# FC_Conn.net
KiCad netlist of a schematic drawn in Altium Designer
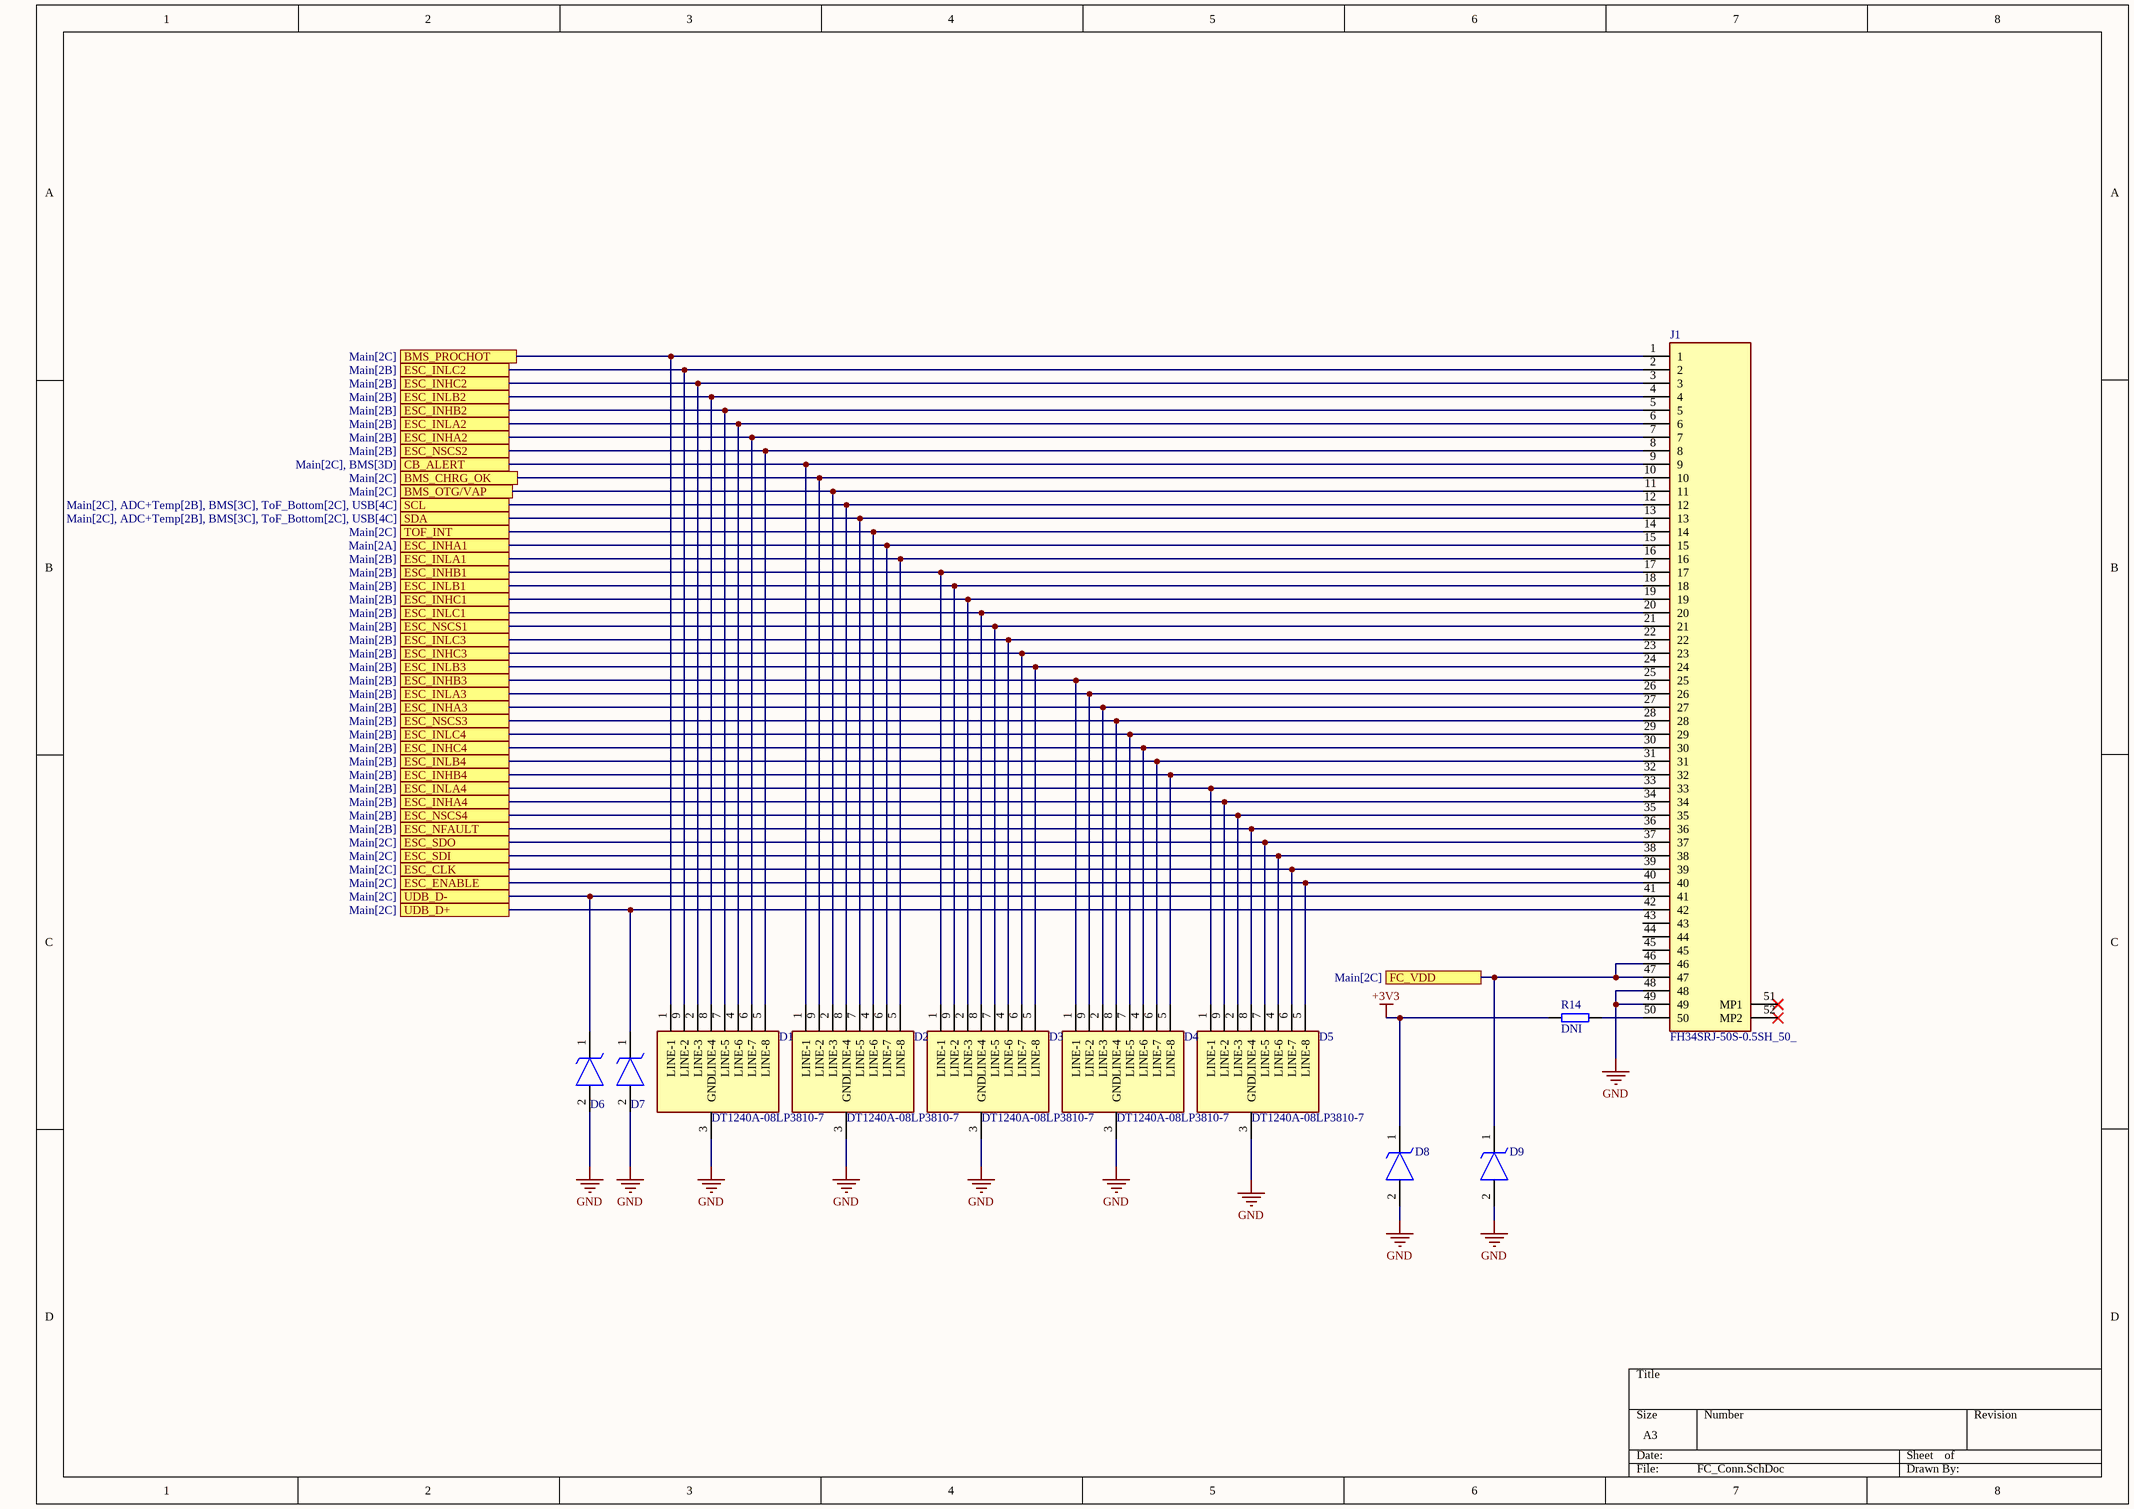
[diagram p0: FC_Conn.SchDoc]

(export (version "E")
  (design (tool "Eeschema 10.0.6"))
  (components
    (comp (ref "D1")
      (value "DT1240A-08LP3810-7")
      (footprint "SamacSys:DT1240A08LP38107")
      (description "TVS Diode (Uni-directional)")
      (fields (field (name "MOUSER PART NUMBER") "621-DT1240A08LP38107"))
      (libsource (lib "SamacSys") (part "DT1240A-08LP3810-7"))
    )
    (comp (ref "D2")
      (value "DT1240A-08LP3810-7")
      (footprint "SamacSys:DT1240A08LP38107")
      (description "TVS Diode (Uni-directional)")
      (fields (field (name "MOUSER PART NUMBER") "621-DT1240A08LP38107"))
      (libsource (lib "SamacSys") (part "DT1240A-08LP3810-7"))
    )
    (comp (ref "D3")
      (value "DT1240A-08LP3810-7")
      (footprint "SamacSys:DT1240A08LP38107")
      (description "TVS Diode (Uni-directional)")
      (fields (field (name "MOUSER PART NUMBER") "621-DT1240A08LP38107"))
      (libsource (lib "SamacSys") (part "DT1240A-08LP3810-7"))
    )
    (comp (ref "D4")
      (value "DT1240A-08LP3810-7")
      (footprint "SamacSys:DT1240A08LP38107")
      (description "TVS Diode (Uni-directional)")
      (fields (field (name "MOUSER PART NUMBER") "621-DT1240A08LP38107"))
      (libsource (lib "SamacSys") (part "DT1240A-08LP3810-7"))
    )
    (comp (ref "D5")
      (value "DT1240A-08LP3810-7")
      (footprint "SamacSys:DT1240A08LP38107")
      (description "TVS Diode (Uni-directional)")
      (fields (field (name "MOUSER PART NUMBER") "621-DT1240A08LP38107"))
      (libsource (lib "SamacSys") (part "DT1240A-08LP3810-7"))
    )
    (comp (ref "D6")
      (value "D1213A-01LP4-7B")
      (footprint "SamacSys:D1213A01LP47B")
      (description "TVS Diode (Uni-directional)")
      (fields (field (name "MOUSER PART NUMBER") "621-D1213A-01LP4-7B"))
      (libsource (lib "*") (part "D1213A-01LP4-7B"))
    )
    (comp (ref "D7")
      (value "D1213A-01LP4-7B")
      (footprint "SamacSys:D1213A01LP47B")
      (description "TVS Diode (Uni-directional)")
      (fields (field (name "MOUSER PART NUMBER") "621-D1213A-01LP4-7B"))
      (libsource (lib "*") (part "D1213A-01LP4-7B"))
    )
    (comp (ref "D8")
      (value "DF2S24FS,L3M")
      (footprint "SamacSys:SODFL1006X45N")
      (description "TVS Diode (Uni-directional)")
      (fields (field (name "MOUSER PART NUMBER") "757-DF2S24FSL3M"))
      (libsource (lib "*") (part "DF2S24FS,L3M"))
    )
    (comp (ref "D9")
      (value "DF2S24FS,L3M")
      (footprint "SamacSys:SODFL1006X45N")
      (description "TVS Diode (Uni-directional)")
      (fields (field (name "MOUSER PART NUMBER") "757-DF2S24FSL3M"))
      (libsource (lib "*") (part "DF2S24FS,L3M"))
    )
    (comp (ref "J1")
      (value "FH34SRJ-50S-0.5SH_50_")
      (footprint "SamacSys:FH34SRJ50S05SH50")
      (description "Connector")
      (fields
        (field (name "MANUFACTURER_PART_NUMBER") "FH34SRJ-50S-0.5SH(50)")
        (field (name "MOUSER PART NUMBER") "798-FH34SRJ50S05SH50")
      )
      (libsource (lib "*") (part "FH34SRJ-50S-0.5SH_50_"))
    )
    (comp (ref "R14")
      (value "DNI")
      (footprint "RES0402")
      (fields (field (name "Comment") "Res0402"))
      (libsource (lib "resistorSMD") (part "Res0402"))
    )
  )
  (nets
    (net (code "1") (name "+3V3") (class "Default")
      (node (ref "D8") (pin "1") (pinfunction "K_1") (pintype "passive"))
      (node (ref "R14") (pin "2") (pinfunction "2_2") (pintype "passive"))
    )
    (net (code "2") (name "/BMS_CHRG_OK") (class "Default")
      (node (ref "D2") (pin "9") (pinfunction "LINE-2_9") (pintype "passive"))
      (node (ref "J1") (pin "10") (pinfunction "10_10") (pintype "passive"))
    )
    (net (code "3") (name "/BMS_OTG{slash}VAP") (class "Default")
      (node (ref "D2") (pin "2") (pinfunction "LINE-3_2") (pintype "passive"))
      (node (ref "J1") (pin "11") (pinfunction "11_11") (pintype "passive"))
    )
    (net (code "4") (name "/BMS_PROCHOT") (class "Default")
      (node (ref "D1") (pin "1") (pinfunction "LINE-1_1") (pintype "passive"))
      (node (ref "J1") (pin "1") (pinfunction "1_1") (pintype "passive"))
    )
    (net (code "5") (name "/CB_ALERT") (class "Default")
      (node (ref "D2") (pin "1") (pinfunction "LINE-1_1") (pintype "passive"))
      (node (ref "J1") (pin "9") (pinfunction "9_9") (pintype "passive"))
    )
    (net (code "6") (name "/ESC_CLK") (class "Default")
      (node (ref "D5") (pin "6") (pinfunction "LINE-7_6") (pintype "passive"))
      (node (ref "J1") (pin "39") (pinfunction "39_39") (pintype "passive"))
    )
    (net (code "7") (name "/ESC_ENABLE") (class "Default")
      (node (ref "D5") (pin "5") (pinfunction "LINE-8_5") (pintype "passive"))
      (node (ref "J1") (pin "40") (pinfunction "40_40") (pintype "passive"))
    )
    (net (code "8") (name "/ESC_INHA1") (class "Default")
      (node (ref "D2") (pin "6") (pinfunction "LINE-7_6") (pintype "passive"))
      (node (ref "J1") (pin "15") (pinfunction "15_15") (pintype "passive"))
    )
    (net (code "9") (name "/ESC_INHA2") (class "Default")
      (node (ref "D1") (pin "6") (pinfunction "LINE-7_6") (pintype "passive"))
      (node (ref "J1") (pin "7") (pinfunction "7_7") (pintype "passive"))
    )
    (net (code "10") (name "/ESC_INHA3") (class "Default")
      (node (ref "D4") (pin "2") (pinfunction "LINE-3_2") (pintype "passive"))
      (node (ref "J1") (pin "27") (pinfunction "27_27") (pintype "passive"))
    )
    (net (code "11") (name "/ESC_INHA4") (class "Default")
      (node (ref "D5") (pin "9") (pinfunction "LINE-2_9") (pintype "passive"))
      (node (ref "J1") (pin "34") (pinfunction "34_34") (pintype "passive"))
    )
    (net (code "12") (name "/ESC_INHB1") (class "Default")
      (node (ref "D3") (pin "1") (pinfunction "LINE-1_1") (pintype "passive"))
      (node (ref "J1") (pin "17") (pinfunction "17_17") (pintype "passive"))
    )
    (net (code "13") (name "/ESC_INHB2") (class "Default")
      (node (ref "D1") (pin "7") (pinfunction "LINE-5_7") (pintype "passive"))
      (node (ref "J1") (pin "5") (pinfunction "5_5") (pintype "passive"))
    )
    (net (code "14") (name "/ESC_INHB3") (class "Default")
      (node (ref "D4") (pin "1") (pinfunction "LINE-1_1") (pintype "passive"))
      (node (ref "J1") (pin "25") (pinfunction "25_25") (pintype "passive"))
    )
    (net (code "15") (name "/ESC_INHB4") (class "Default")
      (node (ref "D4") (pin "5") (pinfunction "LINE-8_5") (pintype "passive"))
      (node (ref "J1") (pin "32") (pinfunction "32_32") (pintype "passive"))
    )
    (net (code "16") (name "/ESC_INHC1") (class "Default")
      (node (ref "D3") (pin "2") (pinfunction "LINE-3_2") (pintype "passive"))
      (node (ref "J1") (pin "19") (pinfunction "19_19") (pintype "passive"))
    )
    (net (code "17") (name "/ESC_INHC2") (class "Default")
      (node (ref "D1") (pin "2") (pinfunction "LINE-3_2") (pintype "passive"))
      (node (ref "J1") (pin "3") (pinfunction "3_3") (pintype "passive"))
    )
    (net (code "18") (name "/ESC_INHC3") (class "Default")
      (node (ref "D3") (pin "6") (pinfunction "LINE-7_6") (pintype "passive"))
      (node (ref "J1") (pin "23") (pinfunction "23_23") (pintype "passive"))
    )
    (net (code "19") (name "/ESC_INHC4") (class "Default")
      (node (ref "D4") (pin "4") (pinfunction "LINE-6_4") (pintype "passive"))
      (node (ref "J1") (pin "30") (pinfunction "30_30") (pintype "passive"))
    )
    (net (code "20") (name "/ESC_INLA1") (class "Default")
      (node (ref "D2") (pin "5") (pinfunction "LINE-8_5") (pintype "passive"))
      (node (ref "J1") (pin "16") (pinfunction "16_16") (pintype "passive"))
    )
    (net (code "21") (name "/ESC_INLA2") (class "Default")
      (node (ref "D1") (pin "4") (pinfunction "LINE-6_4") (pintype "passive"))
      (node (ref "J1") (pin "6") (pinfunction "6_6") (pintype "passive"))
    )
    (net (code "22") (name "/ESC_INLA3") (class "Default")
      (node (ref "D4") (pin "9") (pinfunction "LINE-2_9") (pintype "passive"))
      (node (ref "J1") (pin "26") (pinfunction "26_26") (pintype "passive"))
    )
    (net (code "23") (name "/ESC_INLA4") (class "Default")
      (node (ref "D5") (pin "1") (pinfunction "LINE-1_1") (pintype "passive"))
      (node (ref "J1") (pin "33") (pinfunction "33_33") (pintype "passive"))
    )
    (net (code "24") (name "/ESC_INLB1") (class "Default")
      (node (ref "D3") (pin "9") (pinfunction "LINE-2_9") (pintype "passive"))
      (node (ref "J1") (pin "18") (pinfunction "18_18") (pintype "passive"))
    )
    (net (code "25") (name "/ESC_INLB2") (class "Default")
      (node (ref "D1") (pin "8") (pinfunction "LINE-4_8") (pintype "passive"))
      (node (ref "J1") (pin "4") (pinfunction "4_4") (pintype "passive"))
    )
    (net (code "26") (name "/ESC_INLB3") (class "Default")
      (node (ref "D3") (pin "5") (pinfunction "LINE-8_5") (pintype "passive"))
      (node (ref "J1") (pin "24") (pinfunction "24_24") (pintype "passive"))
    )
    (net (code "27") (name "/ESC_INLB4") (class "Default")
      (node (ref "D4") (pin "6") (pinfunction "LINE-7_6") (pintype "passive"))
      (node (ref "J1") (pin "31") (pinfunction "31_31") (pintype "passive"))
    )
    (net (code "28") (name "/ESC_INLC1") (class "Default")
      (node (ref "D3") (pin "8") (pinfunction "LINE-4_8") (pintype "passive"))
      (node (ref "J1") (pin "20") (pinfunction "20_20") (pintype "passive"))
    )
    (net (code "29") (name "/ESC_INLC2") (class "Default")
      (node (ref "D1") (pin "9") (pinfunction "LINE-2_9") (pintype "passive"))
      (node (ref "J1") (pin "2") (pinfunction "2_2") (pintype "passive"))
    )
    (net (code "30") (name "/ESC_INLC3") (class "Default")
      (node (ref "D3") (pin "4") (pinfunction "LINE-6_4") (pintype "passive"))
      (node (ref "J1") (pin "22") (pinfunction "22_22") (pintype "passive"))
    )
    (net (code "31") (name "/ESC_INLC4") (class "Default")
      (node (ref "D4") (pin "7") (pinfunction "LINE-5_7") (pintype "passive"))
      (node (ref "J1") (pin "29") (pinfunction "29_29") (pintype "passive"))
    )
    (net (code "32") (name "/ESC_NFAULT") (class "Default")
      (node (ref "D5") (pin "8") (pinfunction "LINE-4_8") (pintype "passive"))
      (node (ref "J1") (pin "36") (pinfunction "36_36") (pintype "passive"))
    )
    (net (code "33") (name "/ESC_NSCS1") (class "Default")
      (node (ref "D3") (pin "7") (pinfunction "LINE-5_7") (pintype "passive"))
      (node (ref "J1") (pin "21") (pinfunction "21_21") (pintype "passive"))
    )
    (net (code "34") (name "/ESC_NSCS2") (class "Default")
      (node (ref "D1") (pin "5") (pinfunction "LINE-8_5") (pintype "passive"))
      (node (ref "J1") (pin "8") (pinfunction "8_8") (pintype "passive"))
    )
    (net (code "35") (name "/ESC_NSCS3") (class "Default")
      (node (ref "D4") (pin "8") (pinfunction "LINE-4_8") (pintype "passive"))
      (node (ref "J1") (pin "28") (pinfunction "28_28") (pintype "passive"))
    )
    (net (code "36") (name "/ESC_NSCS4") (class "Default")
      (node (ref "D5") (pin "2") (pinfunction "LINE-3_2") (pintype "passive"))
      (node (ref "J1") (pin "35") (pinfunction "35_35") (pintype "passive"))
    )
    (net (code "37") (name "/ESC_SDI") (class "Default")
      (node (ref "D5") (pin "4") (pinfunction "LINE-6_4") (pintype "passive"))
      (node (ref "J1") (pin "38") (pinfunction "38_38") (pintype "passive"))
    )
    (net (code "38") (name "/ESC_SDO") (class "Default")
      (node (ref "D5") (pin "7") (pinfunction "LINE-5_7") (pintype "passive"))
      (node (ref "J1") (pin "37") (pinfunction "37_37") (pintype "passive"))
    )
    (net (code "39") (name "/FC_VDD") (class "Default")
      (node (ref "D9") (pin "1") (pinfunction "K_1") (pintype "passive"))
      (node (ref "J1") (pin "46") (pinfunction "46_46") (pintype "passive"))
      (node (ref "J1") (pin "47") (pinfunction "47_47") (pintype "passive"))
    )
    (net (code "40") (name "/SCL") (class "Default")
      (node (ref "D2") (pin "8") (pinfunction "LINE-4_8") (pintype "passive"))
      (node (ref "J1") (pin "12") (pinfunction "12_12") (pintype "passive"))
    )
    (net (code "41") (name "/SDA") (class "Default")
      (node (ref "D2") (pin "7") (pinfunction "LINE-5_7") (pintype "passive"))
      (node (ref "J1") (pin "13") (pinfunction "13_13") (pintype "passive"))
    )
    (net (code "42") (name "/TOF_INT") (class "Default")
      (node (ref "D2") (pin "4") (pinfunction "LINE-6_4") (pintype "passive"))
      (node (ref "J1") (pin "14") (pinfunction "14_14") (pintype "passive"))
    )
    (net (code "43") (name "/UDB_D+") (class "Default")
      (node (ref "D7") (pin "1") (pinfunction "K_1") (pintype "passive"))
      (node (ref "J1") (pin "42") (pinfunction "42_42") (pintype "passive"))
    )
    (net (code "44") (name "/UDB_D-") (class "Default")
      (node (ref "D6") (pin "1") (pinfunction "K_1") (pintype "passive"))
      (node (ref "J1") (pin "41") (pinfunction "41_41") (pintype "passive"))
    )
    (net (code "45") (name "GND") (class "Default")
      (node (ref "D1") (pin "3") (pinfunction "GND_3") (pintype "passive"))
      (node (ref "D2") (pin "3") (pinfunction "GND_3") (pintype "passive"))
      (node (ref "D3") (pin "3") (pinfunction "GND_3") (pintype "passive"))
      (node (ref "D4") (pin "3") (pinfunction "GND_3") (pintype "passive"))
      (node (ref "D5") (pin "3") (pinfunction "GND_3") (pintype "passive"))
      (node (ref "D6") (pin "2") (pinfunction "A_2") (pintype "passive"))
      (node (ref "D7") (pin "2") (pinfunction "A_2") (pintype "passive"))
      (node (ref "D8") (pin "2") (pinfunction "A_2") (pintype "passive"))
      (node (ref "D9") (pin "2") (pinfunction "A_2") (pintype "passive"))
      (node (ref "J1") (pin "48") (pinfunction "48_48") (pintype "passive"))
      (node (ref "J1") (pin "49") (pinfunction "49_49") (pintype "passive"))
    )
    (net (code "46") (name "Net-(J1-Pad50)") (class "Default")
      (node (ref "J1") (pin "50") (pinfunction "50_50") (pintype "passive"))
      (node (ref "R14") (pin "1") (pinfunction "1_1") (pintype "passive"))
    )
    (net (code "47") (name "unconnected-(J1-MP1-Pad51)") (class "Default")
      (node (ref "J1") (pin "51") (pinfunction "MP1_51") (pintype "passive+no_connect"))
    )
    (net (code "48") (name "unconnected-(J1-MP2-Pad52)") (class "Default")
      (node (ref "J1") (pin "52") (pinfunction "MP2_52") (pintype "passive+no_connect"))
    )
    (net (code "49") (name "unconnected-(J1-Pad43)") (class "Default")
      (node (ref "J1") (pin "43") (pinfunction "43_43") (pintype "passive"))
    )
    (net (code "50") (name "unconnected-(J1-Pad44)") (class "Default")
      (node (ref "J1") (pin "44") (pinfunction "44_44") (pintype "passive"))
    )
    (net (code "51") (name "unconnected-(J1-Pad45)") (class "Default")
      (node (ref "J1") (pin "45") (pinfunction "45_45") (pintype "passive"))
    )
  )
)
